# Sheet1.net
KiCad netlist of a schematic drawn in Altium Designer
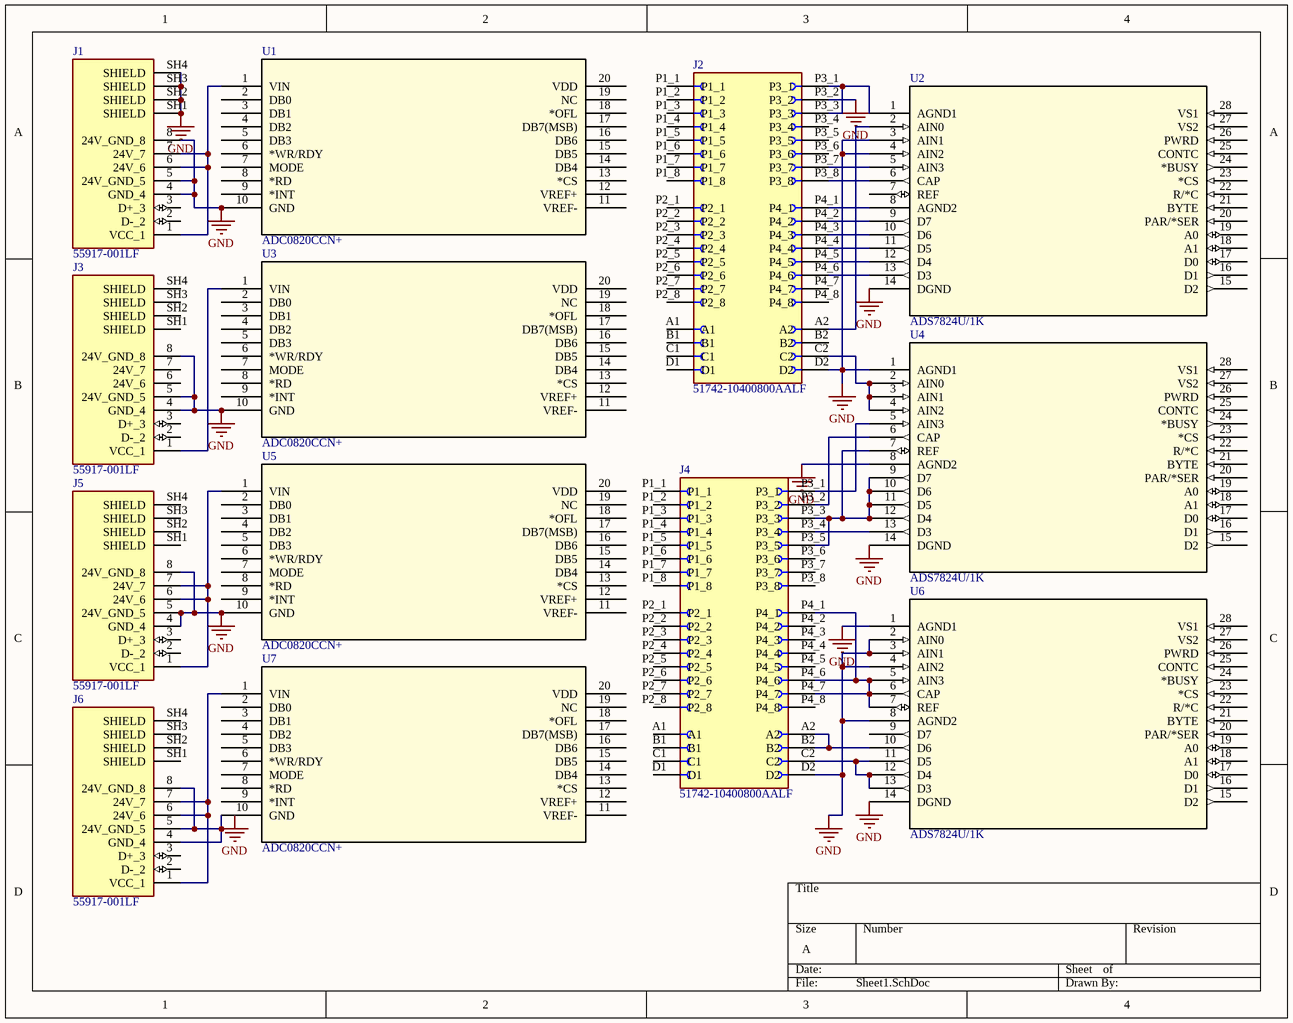
[diagram p0: Sheet1.SchDoc]

(export (version "E")
  (design (tool "Eeschema 10.0.6"))
  (components
    (comp (ref "J1")
      (value "55917-001LF")
      (footprint "AMPHENOL_55917-001LF")
      (libsource (lib "55917-001LF") (part "55917-001LF"))
    )
    (comp (ref "J2")
      (value "51742-10400800AALF")
      (footprint "AMPHENOL_51742-10400800AALF")
      (description "PwrBladeÂ®, Power Supply Connectors, 4P 8S Vertical Receptacle.")
      (fields (field (name "MF") "Amphenol ICC (FCI)"))
      (libsource (lib "51742-10400800AALF") (part "51742-10400800AALF"))
    )
    (comp (ref "J3")
      (value "55917-001LF")
      (footprint "AMPHENOL_55917-001LF")
      (libsource (lib "55917-001LF") (part "55917-001LF"))
    )
    (comp (ref "J4")
      (value "51742-10400800AALF")
      (footprint "AMPHENOL_51742-10400800AALF")
      (description "PwrBladeÂ®, Power Supply Connectors, 4P 8S Vertical Receptacle.")
      (fields (field (name "MF") "Amphenol ICC (FCI)"))
      (libsource (lib "51742-10400800AALF") (part "51742-10400800AALF"))
    )
    (comp (ref "J5")
      (value "55917-001LF")
      (footprint "AMPHENOL_55917-001LF")
      (libsource (lib "55917-001LF") (part "55917-001LF"))
    )
    (comp (ref "J6")
      (value "55917-001LF")
      (footprint "AMPHENOL_55917-001LF")
      (libsource (lib "55917-001LF") (part "55917-001LF"))
    )
    (comp (ref "U1")
      (value "ADC0820CCN+")
      (footprint "21-0043D_20_MXM")
      (description "No Description Available")
      (fields (field (name "COPYRIGHT") "Copyright (C) 2023 Ultra Librarian. All rights reserved."))
      (libsource (lib "ADC0820CCN&plus_") (part "ADC0820CCN+"))
    )
    (comp (ref "U2")
      (value "ADS7824U/1K")
      (footprint "DW28")
      (description "No Description Available")
      (fields (field (name "COPYRIGHT") "Copyright (C) 2023 Ultra Librarian. All rights reserved."))
      (libsource (lib "ADS7824U1K") (part "ADS7824U1K"))
    )
    (comp (ref "U3")
      (value "ADC0820CCN+")
      (footprint "21-0043D_20_MXM")
      (description "No Description Available")
      (fields (field (name "COPYRIGHT") "Copyright (C) 2023 Ultra Librarian. All rights reserved."))
      (libsource (lib "ADC0820CCN&plus_") (part "ADC0820CCN+"))
    )
    (comp (ref "U4")
      (value "ADS7824U/1K")
      (footprint "DW28")
      (description "No Description Available")
      (fields (field (name "COPYRIGHT") "Copyright (C) 2023 Ultra Librarian. All rights reserved."))
      (libsource (lib "ADS7824U1K") (part "ADS7824U1K"))
    )
    (comp (ref "U5")
      (value "ADC0820CCN+")
      (footprint "21-0043D_20_MXM")
      (description "No Description Available")
      (fields (field (name "COPYRIGHT") "Copyright (C) 2023 Ultra Librarian. All rights reserved."))
      (libsource (lib "ADC0820CCN&plus_") (part "ADC0820CCN+"))
    )
    (comp (ref "U6")
      (value "ADS7824U/1K")
      (footprint "DW28")
      (description "No Description Available")
      (fields (field (name "COPYRIGHT") "Copyright (C) 2023 Ultra Librarian. All rights reserved."))
      (libsource (lib "ADS7824U1K") (part "ADS7824U1K"))
    )
    (comp (ref "U7")
      (value "ADC0820CCN+")
      (footprint "21-0043D_20_MXM")
      (description "No Description Available")
      (fields (field (name "COPYRIGHT") "Copyright (C) 2023 Ultra Librarian. All rights reserved."))
      (libsource (lib "ADC0820CCN&plus_") (part "ADC0820CCN+"))
    )
  )
  (nets
    (net (code "1") (name "GND") (class "Default")
      (node (ref "J1") (pin "4") (pinfunction "GND_4_4") (pintype "power_in"))
      (node (ref "J1") (pin "5") (pinfunction "24V_GND_5_5") (pintype "power_in"))
      (node (ref "J1") (pin "8") (pinfunction "24V_GND_8_8") (pintype "power_in"))
      (node (ref "J1") (pin "SH1") (pinfunction "SHIELD_SH1") (pintype "passive"))
      (node (ref "J1") (pin "SH2") (pinfunction "SHIELD_SH2") (pintype "passive"))
      (node (ref "J1") (pin "SH3") (pinfunction "SHIELD_SH3") (pintype "passive"))
      (node (ref "J1") (pin "SH4") (pinfunction "SHIELD_SH4") (pintype "passive"))
      (node (ref "J2") (pin "D2") (pinfunction "D2_D2") (pintype "passive"))
      (node (ref "J2") (pin "P3_2") (pinfunction "P3_2_P3_2") (pintype "power_in"))
      (node (ref "J3") (pin "4") (pinfunction "GND_4_4") (pintype "power_in"))
      (node (ref "J3") (pin "5") (pinfunction "24V_GND_5_5") (pintype "power_in"))
      (node (ref "J3") (pin "8") (pinfunction "24V_GND_8_8") (pintype "power_in"))
      (node (ref "J4") (pin "D2") (pinfunction "D2_D2") (pintype "passive"))
      (node (ref "J5") (pin "4") (pinfunction "GND_4_4") (pintype "power_in"))
      (node (ref "J5") (pin "5") (pinfunction "24V_GND_5_5") (pintype "power_in"))
      (node (ref "J5") (pin "8") (pinfunction "24V_GND_8_8") (pintype "power_in"))
      (node (ref "U1") (pin "10") (pinfunction "GND_10") (pintype "power_in"))
      (node (ref "U2") (pin "14") (pinfunction "DGND_14") (pintype "power_in"))
      (node (ref "U2") (pin "3") (pinfunction "AIN1_3") (pintype "input"))
      (node (ref "U2") (pin "4") (pinfunction "AIN2_4") (pintype "input"))
      (node (ref "U3") (pin "10") (pinfunction "GND_10") (pintype "power_in"))
      (node (ref "U4") (pin "1") (pinfunction "AGND1_1") (pintype "power_in"))
      (node (ref "U4") (pin "14") (pinfunction "DGND_14") (pintype "power_in"))
      (node (ref "U4") (pin "8") (pinfunction "AGND2_8") (pintype "power_in"))
      (node (ref "U5") (pin "10") (pinfunction "GND_10") (pintype "power_in"))
      (node (ref "U6") (pin "1") (pinfunction "AGND1_1") (pintype "power_in"))
      (node (ref "U6") (pin "14") (pinfunction "DGND_14") (pintype "power_in"))
      (node (ref "U6") (pin "2") (pinfunction "AIN0_2") (pintype "input"))
      (node (ref "U6") (pin "3") (pinfunction "AIN1_3") (pintype "input"))
      (node (ref "U6") (pin "4") (pinfunction "AIN2_4") (pintype "input"))
      (node (ref "U6") (pin "8") (pinfunction "AGND2_8") (pintype "power_in"))
    )
    (net (code "2") (name "Net-(J1-24V_6)") (class "Default")
      (node (ref "J1") (pin "1") (pinfunction "VCC_1_1") (pintype "power_in"))
      (node (ref "J1") (pin "6") (pinfunction "24V_6_6") (pintype "power_in"))
      (node (ref "J1") (pin "7") (pinfunction "24V_7_7") (pintype "power_in"))
      (node (ref "U1") (pin "1") (pinfunction "VIN_1") (pintype "passive"))
    )
    (net (code "3") (name "Net-(J3-VCC_1)") (class "Default")
      (node (ref "J3") (pin "1") (pinfunction "VCC_1_1") (pintype "power_in"))
      (node (ref "U3") (pin "1") (pinfunction "VIN_1") (pintype "passive"))
    )
    (net (code "4") (name "Net-(J5-24V_6)") (class "Default")
      (node (ref "J5") (pin "1") (pinfunction "VCC_1_1") (pintype "power_in"))
      (node (ref "J5") (pin "6") (pinfunction "24V_6_6") (pintype "power_in"))
      (node (ref "J5") (pin "7") (pinfunction "24V_7_7") (pintype "power_in"))
      (node (ref "U5") (pin "1") (pinfunction "VIN_1") (pintype "passive"))
    )
    (net (code "5") (name "Net-(J6-24V_6)") (class "Default")
      (node (ref "J6") (pin "1") (pinfunction "VCC_1_1") (pintype "power_in"))
      (node (ref "J6") (pin "6") (pinfunction "24V_6_6") (pintype "power_in"))
      (node (ref "J6") (pin "7") (pinfunction "24V_7_7") (pintype "power_in"))
      (node (ref "U7") (pin "1") (pinfunction "VIN_1") (pintype "passive"))
    )
    (net (code "6") (name "Net-(J6-24V_GND_5)") (class "Default")
      (node (ref "J6") (pin "4") (pinfunction "GND_4_4") (pintype "power_in"))
      (node (ref "J6") (pin "5") (pinfunction "24V_GND_5_5") (pintype "power_in"))
      (node (ref "J6") (pin "8") (pinfunction "24V_GND_8_8") (pintype "power_in"))
      (node (ref "U7") (pin "10") (pinfunction "GND_10") (pintype "power_in"))
    )
    (net (code "7") (name "Net-(U2-AGND1)") (class "Default")
      (node (ref "J2") (pin "P3_1") (pinfunction "P3_1_P3_1") (pintype "power_in"))
      (node (ref "J2") (pin "P3_3") (pinfunction "P3_3_P3_3") (pintype "power_in"))
      (node (ref "U2") (pin "1") (pinfunction "AGND1_1") (pintype "power_in"))
    )
    (net (code "8") (name "Net-(U2-AGND2)") (class "Default")
      (node (ref "J2") (pin "P4_1") (pinfunction "P4_1_P4_1") (pintype "power_in"))
      (node (ref "U2") (pin "8") (pinfunction "AGND2_8") (pintype "power_in"))
    )
    (net (code "9") (name "Net-(U2-AIN0)") (class "Default")
      (node (ref "J2") (pin "A2") (pinfunction "A2_A2") (pintype "passive"))
      (node (ref "U2") (pin "2") (pinfunction "AIN0_2") (pintype "input"))
    )
    (net (code "10") (name "Net-(U2-AIN3)") (class "Default")
      (node (ref "J2") (pin "P3_7") (pinfunction "P3_7_P3_7") (pintype "power_in"))
      (node (ref "U2") (pin "5") (pinfunction "AIN3_5") (pintype "input"))
    )
    (net (code "11") (name "Net-(U2-CAP)") (class "Default")
      (node (ref "J2") (pin "P3_8") (pinfunction "P3_8_P3_8") (pintype "power_in"))
      (node (ref "U2") (pin "6") (pinfunction "CAP_6") (pintype "output"))
    )
    (net (code "12") (name "Net-(U2-D3)") (class "Default")
      (node (ref "J2") (pin "P4_6") (pinfunction "P4_6_P4_6") (pintype "power_in"))
      (node (ref "U2") (pin "13") (pinfunction "D3_13") (pintype "output"))
    )
    (net (code "13") (name "Net-(U2-D4)") (class "Default")
      (node (ref "J2") (pin "P4_5") (pinfunction "P4_5_P4_5") (pintype "power_in"))
      (node (ref "U2") (pin "12") (pinfunction "D4_12") (pintype "output"))
    )
    (net (code "14") (name "Net-(U2-D5)") (class "Default")
      (node (ref "J2") (pin "P4_4") (pinfunction "P4_4_P4_4") (pintype "power_in"))
      (node (ref "U2") (pin "11") (pinfunction "D5_11") (pintype "output"))
    )
    (net (code "15") (name "Net-(U2-D6)") (class "Default")
      (node (ref "J2") (pin "P4_3") (pinfunction "P4_3_P4_3") (pintype "power_in"))
      (node (ref "U2") (pin "10") (pinfunction "D6_10") (pintype "output"))
    )
    (net (code "16") (name "Net-(U2-D7)") (class "Default")
      (node (ref "J2") (pin "P4_2") (pinfunction "P4_2_P4_2") (pintype "power_in"))
      (node (ref "U2") (pin "9") (pinfunction "D7_9") (pintype "output"))
    )
    (net (code "17") (name "Net-(U4-AIN0)") (class "Default")
      (node (ref "J2") (pin "C2") (pinfunction "C2_C2") (pintype "passive"))
      (node (ref "U4") (pin "2") (pinfunction "AIN0_2") (pintype "input"))
      (node (ref "U4") (pin "3") (pinfunction "AIN1_3") (pintype "input"))
      (node (ref "U4") (pin "4") (pinfunction "AIN2_4") (pintype "input"))
    )
    (net (code "18") (name "Net-(U4-AIN3)") (class "Default")
      (node (ref "J4") (pin "P3_1") (pinfunction "P3_1_P3_1") (pintype "power_in"))
      (node (ref "U4") (pin "5") (pinfunction "AIN3_5") (pintype "input"))
    )
    (net (code "19") (name "Net-(U4-CAP)") (class "Default")
      (node (ref "J4") (pin "P3_2") (pinfunction "P3_2_P3_2") (pintype "power_in"))
      (node (ref "U4") (pin "6") (pinfunction "CAP_6") (pintype "output"))
    )
    (net (code "20") (name "Net-(U4-D3)") (class "Default")
      (node (ref "J4") (pin "P3_4") (pinfunction "P3_4_P3_4") (pintype "power_in"))
      (node (ref "U4") (pin "13") (pinfunction "D3_13") (pintype "output"))
    )
    (net (code "21") (name "Net-(U4-D4)") (class "Default")
      (node (ref "J4") (pin "P3_3") (pinfunction "P3_3_P3_3") (pintype "power_in"))
      (node (ref "J4") (pin "P3_5") (pinfunction "P3_5_P3_5") (pintype "power_in"))
      (node (ref "U4") (pin "10") (pinfunction "D6_10") (pintype "output"))
      (node (ref "U4") (pin "11") (pinfunction "D5_11") (pintype "output"))
      (node (ref "U4") (pin "12") (pinfunction "D4_12") (pintype "output"))
      (node (ref "U4") (pin "7") (pinfunction "REF_7") (pintype "bidirectional"))
      (node (ref "U4") (pin "9") (pinfunction "D7_9") (pintype "output"))
    )
    (net (code "22") (name "Net-(U6-AIN3)") (class "Default")
      (node (ref "J4") (pin "P4_1") (pinfunction "P4_1_P4_1") (pintype "power_in"))
      (node (ref "J4") (pin "P4_6") (pinfunction "P4_6_P4_6") (pintype "power_in"))
      (node (ref "J4") (pin "P4_7") (pinfunction "P4_7_P4_7") (pintype "power_in"))
      (node (ref "U6") (pin "5") (pinfunction "AIN3_5") (pintype "input"))
      (node (ref "U6") (pin "6") (pinfunction "CAP_6") (pintype "output"))
      (node (ref "U6") (pin "7") (pinfunction "REF_7") (pintype "bidirectional"))
    )
    (net (code "23") (name "Net-(U6-D3)") (class "Default")
      (node (ref "J4") (pin "C2") (pinfunction "C2_C2") (pintype "passive"))
      (node (ref "U6") (pin "11") (pinfunction "D5_11") (pintype "output"))
      (node (ref "U6") (pin "12") (pinfunction "D4_12") (pintype "output"))
      (node (ref "U6") (pin "13") (pinfunction "D3_13") (pintype "output"))
    )
    (net (code "24") (name "Net-(U6-D6)") (class "Default")
      (node (ref "J4") (pin "A2") (pinfunction "A2_A2") (pintype "passive"))
      (node (ref "J4") (pin "B2") (pinfunction "B2_B2") (pintype "passive"))
      (node (ref "U6") (pin "10") (pinfunction "D6_10") (pintype "output"))
    )
    (net (code "25") (name "unconnected-(J1-D+_3-Pad3)") (class "Default")
      (node (ref "J1") (pin "3") (pinfunction "D+_3_3") (pintype "bidirectional"))
    )
    (net (code "26") (name "unconnected-(J1-D-_2-Pad2)") (class "Default")
      (node (ref "J1") (pin "2") (pinfunction "D-_2_2") (pintype "bidirectional"))
    )
    (net (code "27") (name "unconnected-(J2-PadA1)") (class "Default")
      (node (ref "J2") (pin "A1") (pinfunction "A1_A1") (pintype "passive"))
    )
    (net (code "28") (name "unconnected-(J2-PadB1)") (class "Default")
      (node (ref "J2") (pin "B1") (pinfunction "B1_B1") (pintype "passive"))
    )
    (net (code "29") (name "unconnected-(J2-PadB2)") (class "Default")
      (node (ref "J2") (pin "B2") (pinfunction "B2_B2") (pintype "passive"))
    )
    (net (code "30") (name "unconnected-(J2-PadC1)") (class "Default")
      (node (ref "J2") (pin "C1") (pinfunction "C1_C1") (pintype "passive"))
    )
    (net (code "31") (name "unconnected-(J2-PadD1)") (class "Default")
      (node (ref "J2") (pin "D1") (pinfunction "D1_D1") (pintype "passive"))
    )
    (net (code "32") (name "unconnected-(J2-PadP1_1)") (class "Default")
      (node (ref "J2") (pin "P1_1") (pinfunction "P1_1_P1_1") (pintype "power_in"))
    )
    (net (code "33") (name "unconnected-(J2-PadP1_2)") (class "Default")
      (node (ref "J2") (pin "P1_2") (pinfunction "P1_2_P1_2") (pintype "power_in"))
    )
    (net (code "34") (name "unconnected-(J2-PadP1_3)") (class "Default")
      (node (ref "J2") (pin "P1_3") (pinfunction "P1_3_P1_3") (pintype "power_in"))
    )
    (net (code "35") (name "unconnected-(J2-PadP1_4)") (class "Default")
      (node (ref "J2") (pin "P1_4") (pinfunction "P1_4_P1_4") (pintype "power_in"))
    )
    (net (code "36") (name "unconnected-(J2-PadP1_5)") (class "Default")
      (node (ref "J2") (pin "P1_5") (pinfunction "P1_5_P1_5") (pintype "power_in"))
    )
    (net (code "37") (name "unconnected-(J2-PadP1_6)") (class "Default")
      (node (ref "J2") (pin "P1_6") (pinfunction "P1_6_P1_6") (pintype "power_in"))
    )
    (net (code "38") (name "unconnected-(J2-PadP1_7)") (class "Default")
      (node (ref "J2") (pin "P1_7") (pinfunction "P1_7_P1_7") (pintype "power_in"))
    )
    (net (code "39") (name "unconnected-(J2-PadP1_8)") (class "Default")
      (node (ref "J2") (pin "P1_8") (pinfunction "P1_8_P1_8") (pintype "power_in"))
    )
    (net (code "40") (name "unconnected-(J2-PadP2_1)") (class "Default")
      (node (ref "J2") (pin "P2_1") (pinfunction "P2_1_P2_1") (pintype "power_in"))
    )
    (net (code "41") (name "unconnected-(J2-PadP2_2)") (class "Default")
      (node (ref "J2") (pin "P2_2") (pinfunction "P2_2_P2_2") (pintype "power_in"))
    )
    (net (code "42") (name "unconnected-(J2-PadP2_3)") (class "Default")
      (node (ref "J2") (pin "P2_3") (pinfunction "P2_3_P2_3") (pintype "power_in"))
    )
    (net (code "43") (name "unconnected-(J2-PadP2_4)") (class "Default")
      (node (ref "J2") (pin "P2_4") (pinfunction "P2_4_P2_4") (pintype "power_in"))
    )
    (net (code "44") (name "unconnected-(J2-PadP2_5)") (class "Default")
      (node (ref "J2") (pin "P2_5") (pinfunction "P2_5_P2_5") (pintype "power_in"))
    )
    (net (code "45") (name "unconnected-(J2-PadP2_6)") (class "Default")
      (node (ref "J2") (pin "P2_6") (pinfunction "P2_6_P2_6") (pintype "power_in"))
    )
    (net (code "46") (name "unconnected-(J2-PadP2_7)") (class "Default")
      (node (ref "J2") (pin "P2_7") (pinfunction "P2_7_P2_7") (pintype "power_in"))
    )
    (net (code "47") (name "unconnected-(J2-PadP2_8)") (class "Default")
      (node (ref "J2") (pin "P2_8") (pinfunction "P2_8_P2_8") (pintype "power_in"))
    )
    (net (code "48") (name "unconnected-(J2-PadP3_4)") (class "Default")
      (node (ref "J2") (pin "P3_4") (pinfunction "P3_4_P3_4") (pintype "power_in"))
    )
    (net (code "49") (name "unconnected-(J2-PadP3_5)") (class "Default")
      (node (ref "J2") (pin "P3_5") (pinfunction "P3_5_P3_5") (pintype "power_in"))
    )
    (net (code "50") (name "unconnected-(J2-PadP3_6)") (class "Default")
      (node (ref "J2") (pin "P3_6") (pinfunction "P3_6_P3_6") (pintype "power_in"))
    )
    (net (code "51") (name "unconnected-(J2-PadP4_7)") (class "Default")
      (node (ref "J2") (pin "P4_7") (pinfunction "P4_7_P4_7") (pintype "power_in"))
    )
    (net (code "52") (name "unconnected-(J2-PadP4_8)") (class "Default")
      (node (ref "J2") (pin "P4_8") (pinfunction "P4_8_P4_8") (pintype "power_in"))
    )
    (net (code "53") (name "unconnected-(J3-24V_6-Pad6)") (class "Default")
      (node (ref "J3") (pin "6") (pinfunction "24V_6_6") (pintype "power_in"))
    )
    (net (code "54") (name "unconnected-(J3-24V_7-Pad7)") (class "Default")
      (node (ref "J3") (pin "7") (pinfunction "24V_7_7") (pintype "power_in"))
    )
    (net (code "55") (name "unconnected-(J3-D+_3-Pad3)") (class "Default")
      (node (ref "J3") (pin "3") (pinfunction "D+_3_3") (pintype "bidirectional"))
    )
    (net (code "56") (name "unconnected-(J3-D-_2-Pad2)") (class "Default")
      (node (ref "J3") (pin "2") (pinfunction "D-_2_2") (pintype "bidirectional"))
    )
    (net (code "57") (name "unconnected-(J3-SHIELD-PadSH1)") (class "Default")
      (node (ref "J3") (pin "SH1") (pinfunction "SHIELD_SH1") (pintype "passive"))
    )
    (net (code "58") (name "unconnected-(J3-SHIELD-PadSH2)") (class "Default")
      (node (ref "J3") (pin "SH2") (pinfunction "SHIELD_SH2") (pintype "passive"))
    )
    (net (code "59") (name "unconnected-(J3-SHIELD-PadSH3)") (class "Default")
      (node (ref "J3") (pin "SH3") (pinfunction "SHIELD_SH3") (pintype "passive"))
    )
    (net (code "60") (name "unconnected-(J3-SHIELD-PadSH4)") (class "Default")
      (node (ref "J3") (pin "SH4") (pinfunction "SHIELD_SH4") (pintype "passive"))
    )
    (net (code "61") (name "unconnected-(J4-PadA1)") (class "Default")
      (node (ref "J4") (pin "A1") (pinfunction "A1_A1") (pintype "passive"))
    )
    (net (code "62") (name "unconnected-(J4-PadB1)") (class "Default")
      (node (ref "J4") (pin "B1") (pinfunction "B1_B1") (pintype "passive"))
    )
    (net (code "63") (name "unconnected-(J4-PadC1)") (class "Default")
      (node (ref "J4") (pin "C1") (pinfunction "C1_C1") (pintype "passive"))
    )
    (net (code "64") (name "unconnected-(J4-PadD1)") (class "Default")
      (node (ref "J4") (pin "D1") (pinfunction "D1_D1") (pintype "passive"))
    )
    (net (code "65") (name "unconnected-(J4-PadP1_1)") (class "Default")
      (node (ref "J4") (pin "P1_1") (pinfunction "P1_1_P1_1") (pintype "power_in"))
    )
    (net (code "66") (name "unconnected-(J4-PadP1_2)") (class "Default")
      (node (ref "J4") (pin "P1_2") (pinfunction "P1_2_P1_2") (pintype "power_in"))
    )
    (net (code "67") (name "unconnected-(J4-PadP1_3)") (class "Default")
      (node (ref "J4") (pin "P1_3") (pinfunction "P1_3_P1_3") (pintype "power_in"))
    )
    (net (code "68") (name "unconnected-(J4-PadP1_4)") (class "Default")
      (node (ref "J4") (pin "P1_4") (pinfunction "P1_4_P1_4") (pintype "power_in"))
    )
    (net (code "69") (name "unconnected-(J4-PadP1_5)") (class "Default")
      (node (ref "J4") (pin "P1_5") (pinfunction "P1_5_P1_5") (pintype "power_in"))
    )
    (net (code "70") (name "unconnected-(J4-PadP1_6)") (class "Default")
      (node (ref "J4") (pin "P1_6") (pinfunction "P1_6_P1_6") (pintype "power_in"))
    )
    (net (code "71") (name "unconnected-(J4-PadP1_7)") (class "Default")
      (node (ref "J4") (pin "P1_7") (pinfunction "P1_7_P1_7") (pintype "power_in"))
    )
    (net (code "72") (name "unconnected-(J4-PadP1_8)") (class "Default")
      (node (ref "J4") (pin "P1_8") (pinfunction "P1_8_P1_8") (pintype "power_in"))
    )
    (net (code "73") (name "unconnected-(J4-PadP2_1)") (class "Default")
      (node (ref "J4") (pin "P2_1") (pinfunction "P2_1_P2_1") (pintype "power_in"))
    )
    (net (code "74") (name "unconnected-(J4-PadP2_2)") (class "Default")
      (node (ref "J4") (pin "P2_2") (pinfunction "P2_2_P2_2") (pintype "power_in"))
    )
    (net (code "75") (name "unconnected-(J4-PadP2_3)") (class "Default")
      (node (ref "J4") (pin "P2_3") (pinfunction "P2_3_P2_3") (pintype "power_in"))
    )
    (net (code "76") (name "unconnected-(J4-PadP2_4)") (class "Default")
      (node (ref "J4") (pin "P2_4") (pinfunction "P2_4_P2_4") (pintype "power_in"))
    )
    (net (code "77") (name "unconnected-(J4-PadP2_5)") (class "Default")
      (node (ref "J4") (pin "P2_5") (pinfunction "P2_5_P2_5") (pintype "power_in"))
    )
    (net (code "78") (name "unconnected-(J4-PadP2_6)") (class "Default")
      (node (ref "J4") (pin "P2_6") (pinfunction "P2_6_P2_6") (pintype "power_in"))
    )
    (net (code "79") (name "unconnected-(J4-PadP2_7)") (class "Default")
      (node (ref "J4") (pin "P2_7") (pinfunction "P2_7_P2_7") (pintype "power_in"))
    )
    (net (code "80") (name "unconnected-(J4-PadP2_8)") (class "Default")
      (node (ref "J4") (pin "P2_8") (pinfunction "P2_8_P2_8") (pintype "power_in"))
    )
    (net (code "81") (name "unconnected-(J4-PadP3_6)") (class "Default")
      (node (ref "J4") (pin "P3_6") (pinfunction "P3_6_P3_6") (pintype "power_in"))
    )
    (net (code "82") (name "unconnected-(J4-PadP3_7)") (class "Default")
      (node (ref "J4") (pin "P3_7") (pinfunction "P3_7_P3_7") (pintype "power_in"))
    )
    (net (code "83") (name "unconnected-(J4-PadP3_8)") (class "Default")
      (node (ref "J4") (pin "P3_8") (pinfunction "P3_8_P3_8") (pintype "power_in"))
    )
    (net (code "84") (name "unconnected-(J4-PadP4_2)") (class "Default")
      (node (ref "J4") (pin "P4_2") (pinfunction "P4_2_P4_2") (pintype "power_in"))
    )
    (net (code "85") (name "unconnected-(J4-PadP4_3)") (class "Default")
      (node (ref "J4") (pin "P4_3") (pinfunction "P4_3_P4_3") (pintype "power_in"))
    )
    (net (code "86") (name "unconnected-(J4-PadP4_4)") (class "Default")
      (node (ref "J4") (pin "P4_4") (pinfunction "P4_4_P4_4") (pintype "power_in"))
    )
    (net (code "87") (name "unconnected-(J4-PadP4_5)") (class "Default")
      (node (ref "J4") (pin "P4_5") (pinfunction "P4_5_P4_5") (pintype "power_in"))
    )
    (net (code "88") (name "unconnected-(J4-PadP4_8)") (class "Default")
      (node (ref "J4") (pin "P4_8") (pinfunction "P4_8_P4_8") (pintype "power_in"))
    )
    (net (code "89") (name "unconnected-(J5-D+_3-Pad3)") (class "Default")
      (node (ref "J5") (pin "3") (pinfunction "D+_3_3") (pintype "bidirectional"))
    )
    (net (code "90") (name "unconnected-(J5-D-_2-Pad2)") (class "Default")
      (node (ref "J5") (pin "2") (pinfunction "D-_2_2") (pintype "bidirectional"))
    )
    (net (code "91") (name "unconnected-(J5-SHIELD-PadSH1)") (class "Default")
      (node (ref "J5") (pin "SH1") (pinfunction "SHIELD_SH1") (pintype "passive"))
    )
    (net (code "92") (name "unconnected-(J5-SHIELD-PadSH2)") (class "Default")
      (node (ref "J5") (pin "SH2") (pinfunction "SHIELD_SH2") (pintype "passive"))
    )
    (net (code "93") (name "unconnected-(J5-SHIELD-PadSH3)") (class "Default")
      (node (ref "J5") (pin "SH3") (pinfunction "SHIELD_SH3") (pintype "passive"))
    )
    (net (code "94") (name "unconnected-(J5-SHIELD-PadSH4)") (class "Default")
      (node (ref "J5") (pin "SH4") (pinfunction "SHIELD_SH4") (pintype "passive"))
    )
    (net (code "95") (name "unconnected-(J6-D+_3-Pad3)") (class "Default")
      (node (ref "J6") (pin "3") (pinfunction "D+_3_3") (pintype "bidirectional"))
    )
    (net (code "96") (name "unconnected-(J6-D-_2-Pad2)") (class "Default")
      (node (ref "J6") (pin "2") (pinfunction "D-_2_2") (pintype "bidirectional"))
    )
    (net (code "97") (name "unconnected-(J6-SHIELD-PadSH1)") (class "Default")
      (node (ref "J6") (pin "SH1") (pinfunction "SHIELD_SH1") (pintype "passive"))
    )
    (net (code "98") (name "unconnected-(J6-SHIELD-PadSH2)") (class "Default")
      (node (ref "J6") (pin "SH2") (pinfunction "SHIELD_SH2") (pintype "passive"))
    )
    (net (code "99") (name "unconnected-(J6-SHIELD-PadSH3)") (class "Default")
      (node (ref "J6") (pin "SH3") (pinfunction "SHIELD_SH3") (pintype "passive"))
    )
    (net (code "100") (name "unconnected-(J6-SHIELD-PadSH4)") (class "Default")
      (node (ref "J6") (pin "SH4") (pinfunction "SHIELD_SH4") (pintype "passive"))
    )
    (net (code "101") (name "unconnected-(U1-*CS-Pad13)") (class "Default")
      (node (ref "U1") (pin "13") (pinfunction "*CS_13") (pintype "passive"))
    )
    (net (code "102") (name "unconnected-(U1-*INT-Pad9)") (class "Default")
      (node (ref "U1") (pin "9") (pinfunction "*INT_9") (pintype "passive"))
    )
    (net (code "103") (name "unconnected-(U1-*OFL-Pad18)") (class "Default")
      (node (ref "U1") (pin "18") (pinfunction "*OFL_18") (pintype "passive"))
    )
    (net (code "104") (name "unconnected-(U1-*RD-Pad8)") (class "Default")
      (node (ref "U1") (pin "8") (pinfunction "*RD_8") (pintype "passive"))
    )
    (net (code "105") (name "unconnected-(U1-*WR{slash}RDY-Pad6)") (class "Default")
      (node (ref "U1") (pin "6") (pinfunction "*WR/RDY_6") (pintype "passive"))
    )
    (net (code "106") (name "unconnected-(U1-DB0-Pad2)") (class "Default")
      (node (ref "U1") (pin "2") (pinfunction "DB0_2") (pintype "passive"))
    )
    (net (code "107") (name "unconnected-(U1-DB1-Pad3)") (class "Default")
      (node (ref "U1") (pin "3") (pinfunction "DB1_3") (pintype "passive"))
    )
    (net (code "108") (name "unconnected-(U1-DB2-Pad4)") (class "Default")
      (node (ref "U1") (pin "4") (pinfunction "DB2_4") (pintype "passive"))
    )
    (net (code "109") (name "unconnected-(U1-DB3-Pad5)") (class "Default")
      (node (ref "U1") (pin "5") (pinfunction "DB3_5") (pintype "passive"))
    )
    (net (code "110") (name "unconnected-(U1-DB4-Pad14)") (class "Default")
      (node (ref "U1") (pin "14") (pinfunction "DB4_14") (pintype "passive"))
    )
    (net (code "111") (name "unconnected-(U1-DB5-Pad15)") (class "Default")
      (node (ref "U1") (pin "15") (pinfunction "DB5_15") (pintype "passive"))
    )
    (net (code "112") (name "unconnected-(U1-DB6-Pad16)") (class "Default")
      (node (ref "U1") (pin "16") (pinfunction "DB6_16") (pintype "passive"))
    )
    (net (code "113") (name "unconnected-(U1-DB7(MSB)-Pad17)") (class "Default")
      (node (ref "U1") (pin "17") (pinfunction "DB7(MSB)_17") (pintype "passive"))
    )
    (net (code "114") (name "unconnected-(U1-MODE-Pad7)") (class "Default")
      (node (ref "U1") (pin "7") (pinfunction "MODE_7") (pintype "passive"))
    )
    (net (code "115") (name "unconnected-(U1-NC-Pad19)") (class "Default")
      (node (ref "U1") (pin "19") (pinfunction "NC_19") (pintype "passive"))
    )
    (net (code "116") (name "unconnected-(U1-VDD-Pad20)") (class "Default")
      (node (ref "U1") (pin "20") (pinfunction "VDD_20") (pintype "power_in"))
    )
    (net (code "117") (name "unconnected-(U1-VREF+-Pad12)") (class "Default")
      (node (ref "U1") (pin "12") (pinfunction "VREF+_12") (pintype "passive"))
    )
    (net (code "118") (name "unconnected-(U1-VREF--Pad11)") (class "Default")
      (node (ref "U1") (pin "11") (pinfunction "VREF-_11") (pintype "passive"))
    )
    (net (code "119") (name "unconnected-(U2-*BUSY-Pad24)") (class "Default")
      (node (ref "U2") (pin "24") (pinfunction "*BUSY_24") (pintype "output"))
    )
    (net (code "120") (name "unconnected-(U2-*CS-Pad23)") (class "Default")
      (node (ref "U2") (pin "23") (pinfunction "*CS_23") (pintype "input"))
    )
    (net (code "121") (name "unconnected-(U2-A0-Pad19)") (class "Default")
      (node (ref "U2") (pin "19") (pinfunction "A0_19") (pintype "bidirectional"))
    )
    (net (code "122") (name "unconnected-(U2-A1-Pad18)") (class "Default")
      (node (ref "U2") (pin "18") (pinfunction "A1_18") (pintype "bidirectional"))
    )
    (net (code "123") (name "unconnected-(U2-BYTE-Pad21)") (class "Default")
      (node (ref "U2") (pin "21") (pinfunction "BYTE_21") (pintype "input"))
    )
    (net (code "124") (name "unconnected-(U2-CONTC-Pad25)") (class "Default")
      (node (ref "U2") (pin "25") (pinfunction "CONTC_25") (pintype "input"))
    )
    (net (code "125") (name "unconnected-(U2-D0-Pad17)") (class "Default")
      (node (ref "U2") (pin "17") (pinfunction "D0_17") (pintype "bidirectional"))
    )
    (net (code "126") (name "unconnected-(U2-D1-Pad16)") (class "Default")
      (node (ref "U2") (pin "16") (pinfunction "D1_16") (pintype "output"))
    )
    (net (code "127") (name "unconnected-(U2-D2-Pad15)") (class "Default")
      (node (ref "U2") (pin "15") (pinfunction "D2_15") (pintype "output"))
    )
    (net (code "128") (name "unconnected-(U2-PAR{slash}*SER-Pad20)") (class "Default")
      (node (ref "U2") (pin "20") (pinfunction "PAR/*SER_20") (pintype "input"))
    )
    (net (code "129") (name "unconnected-(U2-PWRD-Pad26)") (class "Default")
      (node (ref "U2") (pin "26") (pinfunction "PWRD_26") (pintype "input"))
    )
    (net (code "130") (name "unconnected-(U2-REF-Pad7)") (class "Default")
      (node (ref "U2") (pin "7") (pinfunction "REF_7") (pintype "bidirectional"))
    )
    (net (code "131") (name "unconnected-(U2-R{slash}*C-Pad22)") (class "Default")
      (node (ref "U2") (pin "22") (pinfunction "R/*C_22") (pintype "input"))
    )
    (net (code "132") (name "unconnected-(U2-VS1-Pad28)") (class "Default")
      (node (ref "U2") (pin "28") (pinfunction "VS1_28") (pintype "input"))
    )
    (net (code "133") (name "unconnected-(U2-VS2-Pad27)") (class "Default")
      (node (ref "U2") (pin "27") (pinfunction "VS2_27") (pintype "input"))
    )
    (net (code "134") (name "unconnected-(U3-*CS-Pad13)") (class "Default")
      (node (ref "U3") (pin "13") (pinfunction "*CS_13") (pintype "passive"))
    )
    (net (code "135") (name "unconnected-(U3-*INT-Pad9)") (class "Default")
      (node (ref "U3") (pin "9") (pinfunction "*INT_9") (pintype "passive"))
    )
    (net (code "136") (name "unconnected-(U3-*OFL-Pad18)") (class "Default")
      (node (ref "U3") (pin "18") (pinfunction "*OFL_18") (pintype "passive"))
    )
    (net (code "137") (name "unconnected-(U3-*RD-Pad8)") (class "Default")
      (node (ref "U3") (pin "8") (pinfunction "*RD_8") (pintype "passive"))
    )
    (net (code "138") (name "unconnected-(U3-*WR{slash}RDY-Pad6)") (class "Default")
      (node (ref "U3") (pin "6") (pinfunction "*WR/RDY_6") (pintype "passive"))
    )
    (net (code "139") (name "unconnected-(U3-DB0-Pad2)") (class "Default")
      (node (ref "U3") (pin "2") (pinfunction "DB0_2") (pintype "passive"))
    )
    (net (code "140") (name "unconnected-(U3-DB1-Pad3)") (class "Default")
      (node (ref "U3") (pin "3") (pinfunction "DB1_3") (pintype "passive"))
    )
    (net (code "141") (name "unconnected-(U3-DB2-Pad4)") (class "Default")
      (node (ref "U3") (pin "4") (pinfunction "DB2_4") (pintype "passive"))
    )
    (net (code "142") (name "unconnected-(U3-DB3-Pad5)") (class "Default")
      (node (ref "U3") (pin "5") (pinfunction "DB3_5") (pintype "passive"))
    )
    (net (code "143") (name "unconnected-(U3-DB4-Pad14)") (class "Default")
      (node (ref "U3") (pin "14") (pinfunction "DB4_14") (pintype "passive"))
    )
    (net (code "144") (name "unconnected-(U3-DB5-Pad15)") (class "Default")
      (node (ref "U3") (pin "15") (pinfunction "DB5_15") (pintype "passive"))
    )
    (net (code "145") (name "unconnected-(U3-DB6-Pad16)") (class "Default")
      (node (ref "U3") (pin "16") (pinfunction "DB6_16") (pintype "passive"))
    )
    (net (code "146") (name "unconnected-(U3-DB7(MSB)-Pad17)") (class "Default")
      (node (ref "U3") (pin "17") (pinfunction "DB7(MSB)_17") (pintype "passive"))
    )
    (net (code "147") (name "unconnected-(U3-MODE-Pad7)") (class "Default")
      (node (ref "U3") (pin "7") (pinfunction "MODE_7") (pintype "passive"))
    )
    (net (code "148") (name "unconnected-(U3-NC-Pad19)") (class "Default")
      (node (ref "U3") (pin "19") (pinfunction "NC_19") (pintype "passive"))
    )
    (net (code "149") (name "unconnected-(U3-VDD-Pad20)") (class "Default")
      (node (ref "U3") (pin "20") (pinfunction "VDD_20") (pintype "power_in"))
    )
    (net (code "150") (name "unconnected-(U3-VREF+-Pad12)") (class "Default")
      (node (ref "U3") (pin "12") (pinfunction "VREF+_12") (pintype "passive"))
    )
    (net (code "151") (name "unconnected-(U3-VREF--Pad11)") (class "Default")
      (node (ref "U3") (pin "11") (pinfunction "VREF-_11") (pintype "passive"))
    )
    (net (code "152") (name "unconnected-(U4-*BUSY-Pad24)") (class "Default")
      (node (ref "U4") (pin "24") (pinfunction "*BUSY_24") (pintype "output"))
    )
    (net (code "153") (name "unconnected-(U4-*CS-Pad23)") (class "Default")
      (node (ref "U4") (pin "23") (pinfunction "*CS_23") (pintype "input"))
    )
    (net (code "154") (name "unconnected-(U4-A0-Pad19)") (class "Default")
      (node (ref "U4") (pin "19") (pinfunction "A0_19") (pintype "bidirectional"))
    )
    (net (code "155") (name "unconnected-(U4-A1-Pad18)") (class "Default")
      (node (ref "U4") (pin "18") (pinfunction "A1_18") (pintype "bidirectional"))
    )
    (net (code "156") (name "unconnected-(U4-BYTE-Pad21)") (class "Default")
      (node (ref "U4") (pin "21") (pinfunction "BYTE_21") (pintype "input"))
    )
    (net (code "157") (name "unconnected-(U4-CONTC-Pad25)") (class "Default")
      (node (ref "U4") (pin "25") (pinfunction "CONTC_25") (pintype "input"))
    )
    (net (code "158") (name "unconnected-(U4-D0-Pad17)") (class "Default")
      (node (ref "U4") (pin "17") (pinfunction "D0_17") (pintype "bidirectional"))
    )
    (net (code "159") (name "unconnected-(U4-D1-Pad16)") (class "Default")
      (node (ref "U4") (pin "16") (pinfunction "D1_16") (pintype "output"))
    )
    (net (code "160") (name "unconnected-(U4-D2-Pad15)") (class "Default")
      (node (ref "U4") (pin "15") (pinfunction "D2_15") (pintype "output"))
    )
    (net (code "161") (name "unconnected-(U4-PAR{slash}*SER-Pad20)") (class "Default")
      (node (ref "U4") (pin "20") (pinfunction "PAR/*SER_20") (pintype "input"))
    )
    (net (code "162") (name "unconnected-(U4-PWRD-Pad26)") (class "Default")
      (node (ref "U4") (pin "26") (pinfunction "PWRD_26") (pintype "input"))
    )
    (net (code "163") (name "unconnected-(U4-R{slash}*C-Pad22)") (class "Default")
      (node (ref "U4") (pin "22") (pinfunction "R/*C_22") (pintype "input"))
    )
    (net (code "164") (name "unconnected-(U4-VS1-Pad28)") (class "Default")
      (node (ref "U4") (pin "28") (pinfunction "VS1_28") (pintype "input"))
    )
    (net (code "165") (name "unconnected-(U4-VS2-Pad27)") (class "Default")
      (node (ref "U4") (pin "27") (pinfunction "VS2_27") (pintype "input"))
    )
    (net (code "166") (name "unconnected-(U5-*CS-Pad13)") (class "Default")
      (node (ref "U5") (pin "13") (pinfunction "*CS_13") (pintype "passive"))
    )
    (net (code "167") (name "unconnected-(U5-*INT-Pad9)") (class "Default")
      (node (ref "U5") (pin "9") (pinfunction "*INT_9") (pintype "passive"))
    )
    (net (code "168") (name "unconnected-(U5-*OFL-Pad18)") (class "Default")
      (node (ref "U5") (pin "18") (pinfunction "*OFL_18") (pintype "passive"))
    )
    (net (code "169") (name "unconnected-(U5-*RD-Pad8)") (class "Default")
      (node (ref "U5") (pin "8") (pinfunction "*RD_8") (pintype "passive"))
    )
    (net (code "170") (name "unconnected-(U5-*WR{slash}RDY-Pad6)") (class "Default")
      (node (ref "U5") (pin "6") (pinfunction "*WR/RDY_6") (pintype "passive"))
    )
    (net (code "171") (name "unconnected-(U5-DB0-Pad2)") (class "Default")
      (node (ref "U5") (pin "2") (pinfunction "DB0_2") (pintype "passive"))
    )
    (net (code "172") (name "unconnected-(U5-DB1-Pad3)") (class "Default")
      (node (ref "U5") (pin "3") (pinfunction "DB1_3") (pintype "passive"))
    )
    (net (code "173") (name "unconnected-(U5-DB2-Pad4)") (class "Default")
      (node (ref "U5") (pin "4") (pinfunction "DB2_4") (pintype "passive"))
    )
    (net (code "174") (name "unconnected-(U5-DB3-Pad5)") (class "Default")
      (node (ref "U5") (pin "5") (pinfunction "DB3_5") (pintype "passive"))
    )
    (net (code "175") (name "unconnected-(U5-DB4-Pad14)") (class "Default")
      (node (ref "U5") (pin "14") (pinfunction "DB4_14") (pintype "passive"))
    )
    (net (code "176") (name "unconnected-(U5-DB5-Pad15)") (class "Default")
      (node (ref "U5") (pin "15") (pinfunction "DB5_15") (pintype "passive"))
    )
    (net (code "177") (name "unconnected-(U5-DB6-Pad16)") (class "Default")
      (node (ref "U5") (pin "16") (pinfunction "DB6_16") (pintype "passive"))
    )
    (net (code "178") (name "unconnected-(U5-DB7(MSB)-Pad17)") (class "Default")
      (node (ref "U5") (pin "17") (pinfunction "DB7(MSB)_17") (pintype "passive"))
    )
    (net (code "179") (name "unconnected-(U5-MODE-Pad7)") (class "Default")
      (node (ref "U5") (pin "7") (pinfunction "MODE_7") (pintype "passive"))
    )
    (net (code "180") (name "unconnected-(U5-NC-Pad19)") (class "Default")
      (node (ref "U5") (pin "19") (pinfunction "NC_19") (pintype "passive"))
    )
    (net (code "181") (name "unconnected-(U5-VDD-Pad20)") (class "Default")
      (node (ref "U5") (pin "20") (pinfunction "VDD_20") (pintype "power_in"))
    )
    (net (code "182") (name "unconnected-(U5-VREF+-Pad12)") (class "Default")
      (node (ref "U5") (pin "12") (pinfunction "VREF+_12") (pintype "passive"))
    )
    (net (code "183") (name "unconnected-(U5-VREF--Pad11)") (class "Default")
      (node (ref "U5") (pin "11") (pinfunction "VREF-_11") (pintype "passive"))
    )
    (net (code "184") (name "unconnected-(U6-*BUSY-Pad24)") (class "Default")
      (node (ref "U6") (pin "24") (pinfunction "*BUSY_24") (pintype "output"))
    )
    (net (code "185") (name "unconnected-(U6-*CS-Pad23)") (class "Default")
      (node (ref "U6") (pin "23") (pinfunction "*CS_23") (pintype "input"))
    )
    (net (code "186") (name "unconnected-(U6-A0-Pad19)") (class "Default")
      (node (ref "U6") (pin "19") (pinfunction "A0_19") (pintype "bidirectional"))
    )
    (net (code "187") (name "unconnected-(U6-A1-Pad18)") (class "Default")
      (node (ref "U6") (pin "18") (pinfunction "A1_18") (pintype "bidirectional"))
    )
    (net (code "188") (name "unconnected-(U6-BYTE-Pad21)") (class "Default")
      (node (ref "U6") (pin "21") (pinfunction "BYTE_21") (pintype "input"))
    )
    (net (code "189") (name "unconnected-(U6-CONTC-Pad25)") (class "Default")
      (node (ref "U6") (pin "25") (pinfunction "CONTC_25") (pintype "input"))
    )
    (net (code "190") (name "unconnected-(U6-D0-Pad17)") (class "Default")
      (node (ref "U6") (pin "17") (pinfunction "D0_17") (pintype "bidirectional"))
    )
    (net (code "191") (name "unconnected-(U6-D1-Pad16)") (class "Default")
      (node (ref "U6") (pin "16") (pinfunction "D1_16") (pintype "output"))
    )
    (net (code "192") (name "unconnected-(U6-D2-Pad15)") (class "Default")
      (node (ref "U6") (pin "15") (pinfunction "D2_15") (pintype "output"))
    )
    (net (code "193") (name "unconnected-(U6-D7-Pad9)") (class "Default")
      (node (ref "U6") (pin "9") (pinfunction "D7_9") (pintype "output"))
    )
    (net (code "194") (name "unconnected-(U6-PAR{slash}*SER-Pad20)") (class "Default")
      (node (ref "U6") (pin "20") (pinfunction "PAR/*SER_20") (pintype "input"))
    )
    (net (code "195") (name "unconnected-(U6-PWRD-Pad26)") (class "Default")
      (node (ref "U6") (pin "26") (pinfunction "PWRD_26") (pintype "input"))
    )
    (net (code "196") (name "unconnected-(U6-R{slash}*C-Pad22)") (class "Default")
      (node (ref "U6") (pin "22") (pinfunction "R/*C_22") (pintype "input"))
    )
    (net (code "197") (name "unconnected-(U6-VS1-Pad28)") (class "Default")
      (node (ref "U6") (pin "28") (pinfunction "VS1_28") (pintype "input"))
    )
    (net (code "198") (name "unconnected-(U6-VS2-Pad27)") (class "Default")
      (node (ref "U6") (pin "27") (pinfunction "VS2_27") (pintype "input"))
    )
    (net (code "199") (name "unconnected-(U7-*CS-Pad13)") (class "Default")
      (node (ref "U7") (pin "13") (pinfunction "*CS_13") (pintype "passive"))
    )
    (net (code "200") (name "unconnected-(U7-*INT-Pad9)") (class "Default")
      (node (ref "U7") (pin "9") (pinfunction "*INT_9") (pintype "passive"))
    )
    (net (code "201") (name "unconnected-(U7-*OFL-Pad18)") (class "Default")
      (node (ref "U7") (pin "18") (pinfunction "*OFL_18") (pintype "passive"))
    )
    (net (code "202") (name "unconnected-(U7-*RD-Pad8)") (class "Default")
      (node (ref "U7") (pin "8") (pinfunction "*RD_8") (pintype "passive"))
    )
    (net (code "203") (name "unconnected-(U7-*WR{slash}RDY-Pad6)") (class "Default")
      (node (ref "U7") (pin "6") (pinfunction "*WR/RDY_6") (pintype "passive"))
    )
    (net (code "204") (name "unconnected-(U7-DB0-Pad2)") (class "Default")
      (node (ref "U7") (pin "2") (pinfunction "DB0_2") (pintype "passive"))
    )
    (net (code "205") (name "unconnected-(U7-DB1-Pad3)") (class "Default")
      (node (ref "U7") (pin "3") (pinfunction "DB1_3") (pintype "passive"))
    )
    (net (code "206") (name "unconnected-(U7-DB2-Pad4)") (class "Default")
      (node (ref "U7") (pin "4") (pinfunction "DB2_4") (pintype "passive"))
    )
    (net (code "207") (name "unconnected-(U7-DB3-Pad5)") (class "Default")
      (node (ref "U7") (pin "5") (pinfunction "DB3_5") (pintype "passive"))
    )
    (net (code "208") (name "unconnected-(U7-DB4-Pad14)") (class "Default")
      (node (ref "U7") (pin "14") (pinfunction "DB4_14") (pintype "passive"))
    )
    (net (code "209") (name "unconnected-(U7-DB5-Pad15)") (class "Default")
      (node (ref "U7") (pin "15") (pinfunction "DB5_15") (pintype "passive"))
    )
    (net (code "210") (name "unconnected-(U7-DB6-Pad16)") (class "Default")
      (node (ref "U7") (pin "16") (pinfunction "DB6_16") (pintype "passive"))
    )
    (net (code "211") (name "unconnected-(U7-DB7(MSB)-Pad17)") (class "Default")
      (node (ref "U7") (pin "17") (pinfunction "DB7(MSB)_17") (pintype "passive"))
    )
    (net (code "212") (name "unconnected-(U7-MODE-Pad7)") (class "Default")
      (node (ref "U7") (pin "7") (pinfunction "MODE_7") (pintype "passive"))
    )
    (net (code "213") (name "unconnected-(U7-NC-Pad19)") (class "Default")
      (node (ref "U7") (pin "19") (pinfunction "NC_19") (pintype "passive"))
    )
    (net (code "214") (name "unconnected-(U7-VDD-Pad20)") (class "Default")
      (node (ref "U7") (pin "20") (pinfunction "VDD_20") (pintype "power_in"))
    )
    (net (code "215") (name "unconnected-(U7-VREF+-Pad12)") (class "Default")
      (node (ref "U7") (pin "12") (pinfunction "VREF+_12") (pintype "passive"))
    )
    (net (code "216") (name "unconnected-(U7-VREF--Pad11)") (class "Default")
      (node (ref "U7") (pin "11") (pinfunction "VREF-_11") (pintype "passive"))
    )
  )
)
